# ToolHeadAdapter2.net
KiCad netlist of a schematic drawn in EAGLE
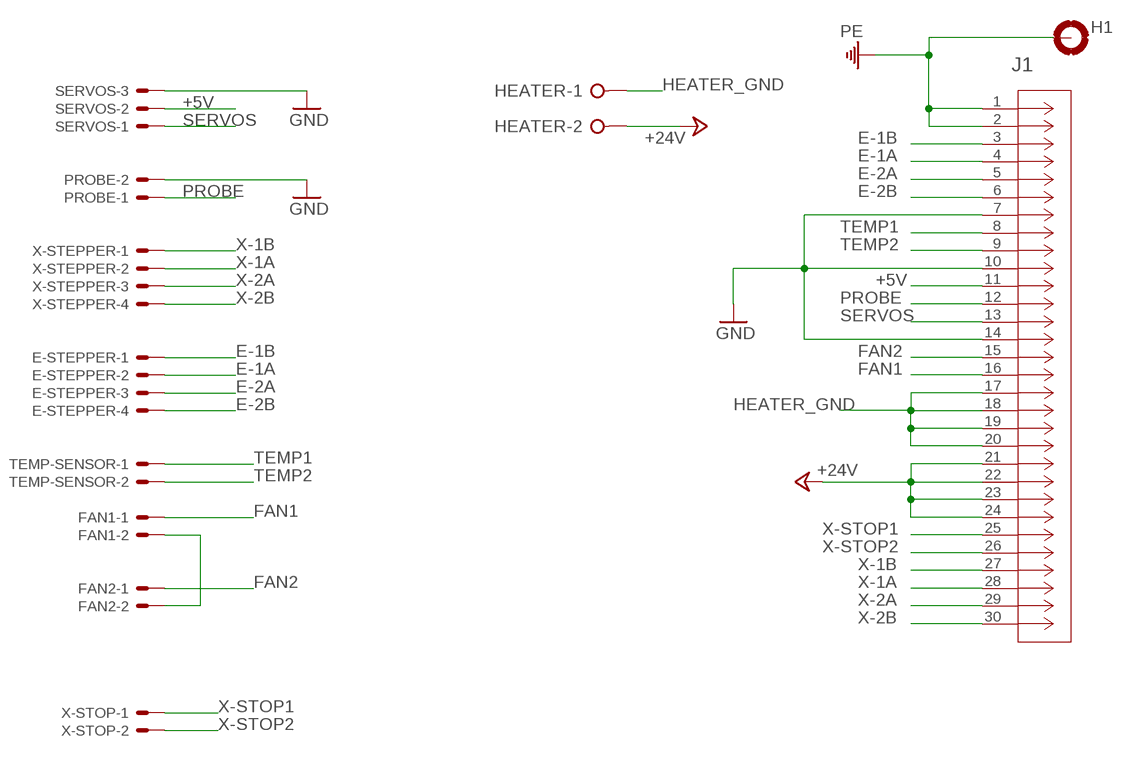
[diagram p0: schematic, sheet 1]

(export (version "E")
  (design (tool "Eeschema 10.0.6"))
  (components
    (comp (ref "E-STEPPER")
      (value "JST-XH-04-PIN-LONG-PAD")
      (footprint "eagle-import:JST-XH-04-PACKAGE-LONG-PAD")
      (libsource (lib "eagle-import") (part "JST-XH-04-PIN-LONG-PAD"))
    )
    (comp (ref "FAN1")
      (value "JST-XH-02-PIN-LONG-PAD")
      (footprint "eagle-import:JST-XH-02-PACKAGE-LONG-PAD")
      (libsource (lib "eagle-import") (part "JST-XH-02-PIN-LONG-PAD"))
    )
    (comp (ref "FAN2")
      (value "JST-XH-02-PIN-LONG-PAD")
      (footprint "eagle-import:JST-XH-02-PACKAGE-LONG-PAD")
      (libsource (lib "eagle-import") (part "JST-XH-02-PIN-LONG-PAD"))
    )
    (comp (ref "H1")
      (value "MOUNT-PAD-ROUND3.2")
      (footprint "eagle-import:3,2-PAD")
      (libsource (lib "eagle-import") (part "MOUNT-PAD-ROUND3.2"))
    )
    (comp (ref "HEATER")
      (value "W237-02P")
      (footprint "eagle-import:W237-132")
      (libsource (lib "eagle-import") (part "W237-02P"))
    )
    (comp (ref "J1")
      (value "EHT-115-01-S-D")
      (footprint "eagle-import:CONN30_15-01-F-D_SAI")
      (fields (field (name "COPYRIGHT") "Copyright (C) 2022 Ultra Librarian. All rights reserved."))
      (libsource (lib "eagle-import") (part "EHT-115-01-S-D"))
    )
    (comp (ref "PROBE")
      (value "JST-XH-02-PIN-LONG-PAD")
      (footprint "eagle-import:JST-XH-02-PACKAGE-LONG-PAD")
      (libsource (lib "eagle-import") (part "JST-XH-02-PIN-LONG-PAD"))
    )
    (comp (ref "SERVOS")
      (value "JST-XH-03-PIN-LONG-PAD")
      (footprint "eagle-import:JST-XH-03-PACKAGE-LONG-PAD")
      (libsource (lib "eagle-import") (part "JST-XH-03-PIN-LONG-PAD"))
    )
    (comp (ref "TEMP-SENSOR")
      (value "JST-XH-02-PIN-LONG-PAD")
      (footprint "eagle-import:JST-XH-02-PACKAGE-LONG-PAD")
      (libsource (lib "eagle-import") (part "JST-XH-02-PIN-LONG-PAD"))
    )
    (comp (ref "X-STEPPER")
      (value "JST-XH-04-PIN-LONG-PAD")
      (footprint "eagle-import:JST-XH-04-PACKAGE-LONG-PAD")
      (libsource (lib "eagle-import") (part "JST-XH-04-PIN-LONG-PAD"))
    )
    (comp (ref "X-STOP")
      (value "JST-XH-02-PIN-LONG-PAD")
      (footprint "eagle-import:JST-XH-02-PACKAGE-LONG-PAD")
      (libsource (lib "eagle-import") (part "JST-XH-02-PIN-LONG-PAD"))
    )
  )
  (nets
    (net (code "1") (name "+24V") (class "Default")
      (node (ref "HEATER") (pin "2") (pinfunction "KL_2") (pintype "passive"))
      (node (ref "J1") (pin "21") (pinfunction "21_21") (pintype "passive"))
      (node (ref "J1") (pin "22") (pinfunction "22_22") (pintype "passive"))
      (node (ref "J1") (pin "23") (pinfunction "23_23") (pintype "passive"))
      (node (ref "J1") (pin "24") (pinfunction "24_24") (pintype "passive"))
    )
    (net (code "2") (name "/+5V") (class "Default")
      (node (ref "J1") (pin "11") (pinfunction "11_11") (pintype "passive"))
      (node (ref "SERVOS") (pin "2") (pinfunction "S_2") (pintype "passive"))
    )
    (net (code "3") (name "/E-1A") (class "Default")
      (node (ref "E-STEPPER") (pin "2") (pinfunction "S_2") (pintype "passive"))
      (node (ref "J1") (pin "4") (pinfunction "4_4") (pintype "passive"))
    )
    (net (code "4") (name "/E-1B") (class "Default")
      (node (ref "E-STEPPER") (pin "1") (pinfunction "S_1") (pintype "passive"))
      (node (ref "J1") (pin "3") (pinfunction "3_3") (pintype "passive"))
    )
    (net (code "5") (name "/E-2A") (class "Default")
      (node (ref "E-STEPPER") (pin "3") (pinfunction "S_3") (pintype "passive"))
      (node (ref "J1") (pin "5") (pinfunction "5_5") (pintype "passive"))
    )
    (net (code "6") (name "/E-2B") (class "Default")
      (node (ref "E-STEPPER") (pin "4") (pinfunction "S_4") (pintype "passive"))
      (node (ref "J1") (pin "6") (pinfunction "6_6") (pintype "passive"))
    )
    (net (code "7") (name "/FAN1") (class "Default")
      (node (ref "FAN1") (pin "1") (pinfunction "S_1") (pintype "passive"))
      (node (ref "J1") (pin "16") (pinfunction "16_16") (pintype "passive"))
    )
    (net (code "8") (name "/FAN2") (class "Default")
      (node (ref "FAN2") (pin "1") (pinfunction "S_1") (pintype "passive"))
      (node (ref "J1") (pin "15") (pinfunction "15_15") (pintype "passive"))
    )
    (net (code "9") (name "/HEATER_GND") (class "Default")
      (node (ref "HEATER") (pin "1") (pinfunction "KL_1") (pintype "passive"))
      (node (ref "J1") (pin "17") (pinfunction "17_17") (pintype "passive"))
      (node (ref "J1") (pin "18") (pinfunction "18_18") (pintype "passive"))
      (node (ref "J1") (pin "19") (pinfunction "19_19") (pintype "passive"))
      (node (ref "J1") (pin "20") (pinfunction "20_20") (pintype "passive"))
    )
    (net (code "10") (name "/PROBE") (class "Default")
      (node (ref "J1") (pin "12") (pinfunction "12_12") (pintype "passive"))
      (node (ref "PROBE") (pin "1") (pinfunction "S_1") (pintype "passive"))
    )
    (net (code "11") (name "/SERVOS") (class "Default")
      (node (ref "J1") (pin "13") (pinfunction "13_13") (pintype "passive"))
      (node (ref "SERVOS") (pin "1") (pinfunction "S_1") (pintype "passive"))
    )
    (net (code "12") (name "/TEMP1") (class "Default")
      (node (ref "J1") (pin "8") (pinfunction "8_8") (pintype "passive"))
      (node (ref "TEMP-SENSOR") (pin "1") (pinfunction "S_1") (pintype "passive"))
    )
    (net (code "13") (name "/TEMP2") (class "Default")
      (node (ref "J1") (pin "9") (pinfunction "9_9") (pintype "passive"))
      (node (ref "TEMP-SENSOR") (pin "2") (pinfunction "S_2") (pintype "passive"))
    )
    (net (code "14") (name "/X-1A") (class "Default")
      (node (ref "J1") (pin "28") (pinfunction "28_28") (pintype "passive"))
      (node (ref "X-STEPPER") (pin "2") (pinfunction "S_2") (pintype "passive"))
    )
    (net (code "15") (name "/X-1B") (class "Default")
      (node (ref "J1") (pin "27") (pinfunction "27_27") (pintype "passive"))
      (node (ref "X-STEPPER") (pin "1") (pinfunction "S_1") (pintype "passive"))
    )
    (net (code "16") (name "/X-2A") (class "Default")
      (node (ref "J1") (pin "29") (pinfunction "29_29") (pintype "passive"))
      (node (ref "X-STEPPER") (pin "3") (pinfunction "S_3") (pintype "passive"))
    )
    (net (code "17") (name "/X-2B") (class "Default")
      (node (ref "J1") (pin "30") (pinfunction "30_30") (pintype "passive"))
      (node (ref "X-STEPPER") (pin "4") (pinfunction "S_4") (pintype "passive"))
    )
    (net (code "18") (name "/X-STOP1") (class "Default")
      (node (ref "J1") (pin "25") (pinfunction "25_25") (pintype "passive"))
      (node (ref "X-STOP") (pin "1") (pinfunction "S_1") (pintype "passive"))
    )
    (net (code "19") (name "/X-STOP2") (class "Default")
      (node (ref "J1") (pin "26") (pinfunction "26_26") (pintype "passive"))
      (node (ref "X-STOP") (pin "2") (pinfunction "S_2") (pintype "passive"))
    )
    (net (code "20") (name "GND") (class "Default")
      (node (ref "J1") (pin "10") (pinfunction "10_10") (pintype "passive"))
      (node (ref "J1") (pin "14") (pinfunction "14_14") (pintype "passive"))
      (node (ref "J1") (pin "7") (pinfunction "7_7") (pintype "passive"))
      (node (ref "PROBE") (pin "2") (pinfunction "S_2") (pintype "passive"))
      (node (ref "SERVOS") (pin "3") (pinfunction "S_3") (pintype "passive"))
    )
    (net (code "21") (name "Net-(FAN1B-S)") (class "Default")
      (node (ref "FAN1") (pin "2") (pinfunction "S_2") (pintype "passive"))
      (node (ref "FAN2") (pin "2") (pinfunction "S_2") (pintype "passive"))
    )
    (net (code "22") (name "PE") (class "Default")
      (node (ref "H1") (pin "B3,2") (pinfunction "MOUNT_B3,2") (pintype "passive"))
      (node (ref "J1") (pin "1") (pinfunction "1_1") (pintype "passive"))
      (node (ref "J1") (pin "2") (pinfunction "2_2") (pintype "passive"))
    )
  )
)
